# module_CC1101.net
KiCad netlist of a schematic drawn in EAGLE
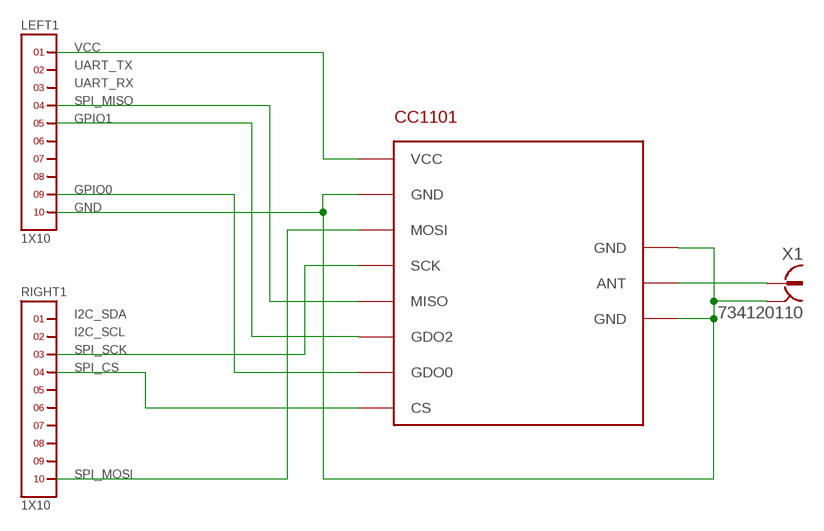
[diagram p0: schematic, sheet 1]

(export (version "E")
  (design (tool "Eeschema 10.0.6"))
  (components
    (comp (ref "CC1101")
      (value "CC1101")
      (footprint "eagle-import:CC1101")
      (libsource (lib "eagle-import") (part "CC1101"))
    )
    (comp (ref "LEFT1")
      (value "1X10")
      (footprint "eagle-import:1X10")
      (libsource (lib "eagle-import") (part "1X10"))
    )
    (comp (ref "RIGHT1")
      (value "1X10")
      (footprint "eagle-import:1X10")
      (libsource (lib "eagle-import") (part "1X10"))
    )
    (comp (ref "X1")
      (value "734120110")
      (footprint "eagle-import:734120110")
      (libsource (lib "eagle-import") (part "734120110"))
    )
  )
  (nets
    (net (code "1") (name "Net-(CC1101-GND-PadGND@1)") (class "Default")
      (node (ref "CC1101") (pin "GND@1") (pinfunction "GND_GND@1") (pintype "bidirectional"))
      (node (ref "CC1101") (pin "GND@2") (pinfunction "GND_GND@2") (pintype "bidirectional"))
      (node (ref "CC1101") (pin "GND@3") (pinfunction "GND_GND@3") (pintype "bidirectional"))
      (node (ref "LEFT1") (pin "10") (pinfunction "10_10") (pintype "bidirectional"))
      (node (ref "X1") (pin "S@1") (pinfunction "2_S@1") (pintype "passive"))
      (node (ref "X1") (pin "S@2") (pinfunction "2_S@2") (pintype "passive"))
      (node (ref "X1") (pin "S@3") (pinfunction "2_S@3") (pintype "passive"))
    )
    (net (code "2") (name "Net-(CC1101-PadANT)") (class "Default")
      (node (ref "CC1101") (pin "ANT") (pinfunction "ANT_ANT") (pintype "bidirectional"))
      (node (ref "X1") (pin "1") (pinfunction "1_1") (pintype "passive"))
    )
    (net (code "3") (name "Net-(CC1101-PadCS)") (class "Default")
      (node (ref "CC1101") (pin "CS") (pinfunction "CS_CS") (pintype "bidirectional"))
      (node (ref "RIGHT1") (pin "4") (pinfunction "4_4") (pintype "bidirectional"))
    )
    (net (code "4") (name "Net-(CC1101-PadGDO0)") (class "Default")
      (node (ref "CC1101") (pin "GDO0") (pinfunction "GDO0_GDO0") (pintype "bidirectional"))
      (node (ref "LEFT1") (pin "9") (pinfunction "9_9") (pintype "bidirectional"))
    )
    (net (code "5") (name "Net-(CC1101-PadGDO2)") (class "Default")
      (node (ref "CC1101") (pin "GDO2") (pinfunction "GDO2_GDO2") (pintype "bidirectional"))
      (node (ref "LEFT1") (pin "5") (pinfunction "5_5") (pintype "bidirectional"))
    )
    (net (code "6") (name "Net-(CC1101-PadMISO)") (class "Default")
      (node (ref "CC1101") (pin "MISO") (pinfunction "MISO_MISO") (pintype "bidirectional"))
      (node (ref "LEFT1") (pin "4") (pinfunction "4_4") (pintype "bidirectional"))
    )
    (net (code "7") (name "Net-(CC1101-PadMOSI)") (class "Default")
      (node (ref "CC1101") (pin "MOSI") (pinfunction "MOSI_MOSI") (pintype "bidirectional"))
      (node (ref "RIGHT1") (pin "10") (pinfunction "10_10") (pintype "bidirectional"))
    )
    (net (code "8") (name "Net-(CC1101-PadSCK)") (class "Default")
      (node (ref "CC1101") (pin "SCK") (pinfunction "SCK_SCK") (pintype "bidirectional"))
      (node (ref "RIGHT1") (pin "3") (pinfunction "3_3") (pintype "bidirectional"))
    )
    (net (code "9") (name "Net-(CC1101-PadVCC)") (class "Default")
      (node (ref "CC1101") (pin "VCC") (pinfunction "VCC_VCC") (pintype "bidirectional"))
      (node (ref "LEFT1") (pin "1") (pinfunction "1_1") (pintype "bidirectional"))
    )
    (net (code "10") (name "unconnected-(LEFT1-Pad2)") (class "Default")
      (node (ref "LEFT1") (pin "2") (pinfunction "2_2") (pintype "bidirectional"))
    )
    (net (code "11") (name "unconnected-(LEFT1-Pad3)") (class "Default")
      (node (ref "LEFT1") (pin "3") (pinfunction "3_3") (pintype "bidirectional"))
    )
    (net (code "12") (name "unconnected-(LEFT1-Pad6)") (class "Default")
      (node (ref "LEFT1") (pin "6") (pinfunction "6_6") (pintype "bidirectional"))
    )
    (net (code "13") (name "unconnected-(LEFT1-Pad7)") (class "Default")
      (node (ref "LEFT1") (pin "7") (pinfunction "7_7") (pintype "bidirectional"))
    )
    (net (code "14") (name "unconnected-(LEFT1-Pad8)") (class "Default")
      (node (ref "LEFT1") (pin "8") (pinfunction "8_8") (pintype "bidirectional"))
    )
    (net (code "15") (name "unconnected-(RIGHT1-Pad1)") (class "Default")
      (node (ref "RIGHT1") (pin "1") (pinfunction "1_1") (pintype "bidirectional"))
    )
    (net (code "16") (name "unconnected-(RIGHT1-Pad2)") (class "Default")
      (node (ref "RIGHT1") (pin "2") (pinfunction "2_2") (pintype "bidirectional"))
    )
    (net (code "17") (name "unconnected-(RIGHT1-Pad5)") (class "Default")
      (node (ref "RIGHT1") (pin "5") (pinfunction "5_5") (pintype "bidirectional"))
    )
    (net (code "18") (name "unconnected-(RIGHT1-Pad6)") (class "Default")
      (node (ref "RIGHT1") (pin "6") (pinfunction "6_6") (pintype "bidirectional"))
    )
    (net (code "19") (name "unconnected-(RIGHT1-Pad7)") (class "Default")
      (node (ref "RIGHT1") (pin "7") (pinfunction "7_7") (pintype "bidirectional"))
    )
    (net (code "20") (name "unconnected-(RIGHT1-Pad8)") (class "Default")
      (node (ref "RIGHT1") (pin "8") (pinfunction "8_8") (pintype "bidirectional"))
    )
    (net (code "21") (name "unconnected-(RIGHT1-Pad9)") (class "Default")
      (node (ref "RIGHT1") (pin "9") (pinfunction "9_9") (pintype "bidirectional"))
    )
  )
)
